# zs-pentagon-dip_0.net
KiCad netlist of a schematic drawn in Altium Designer
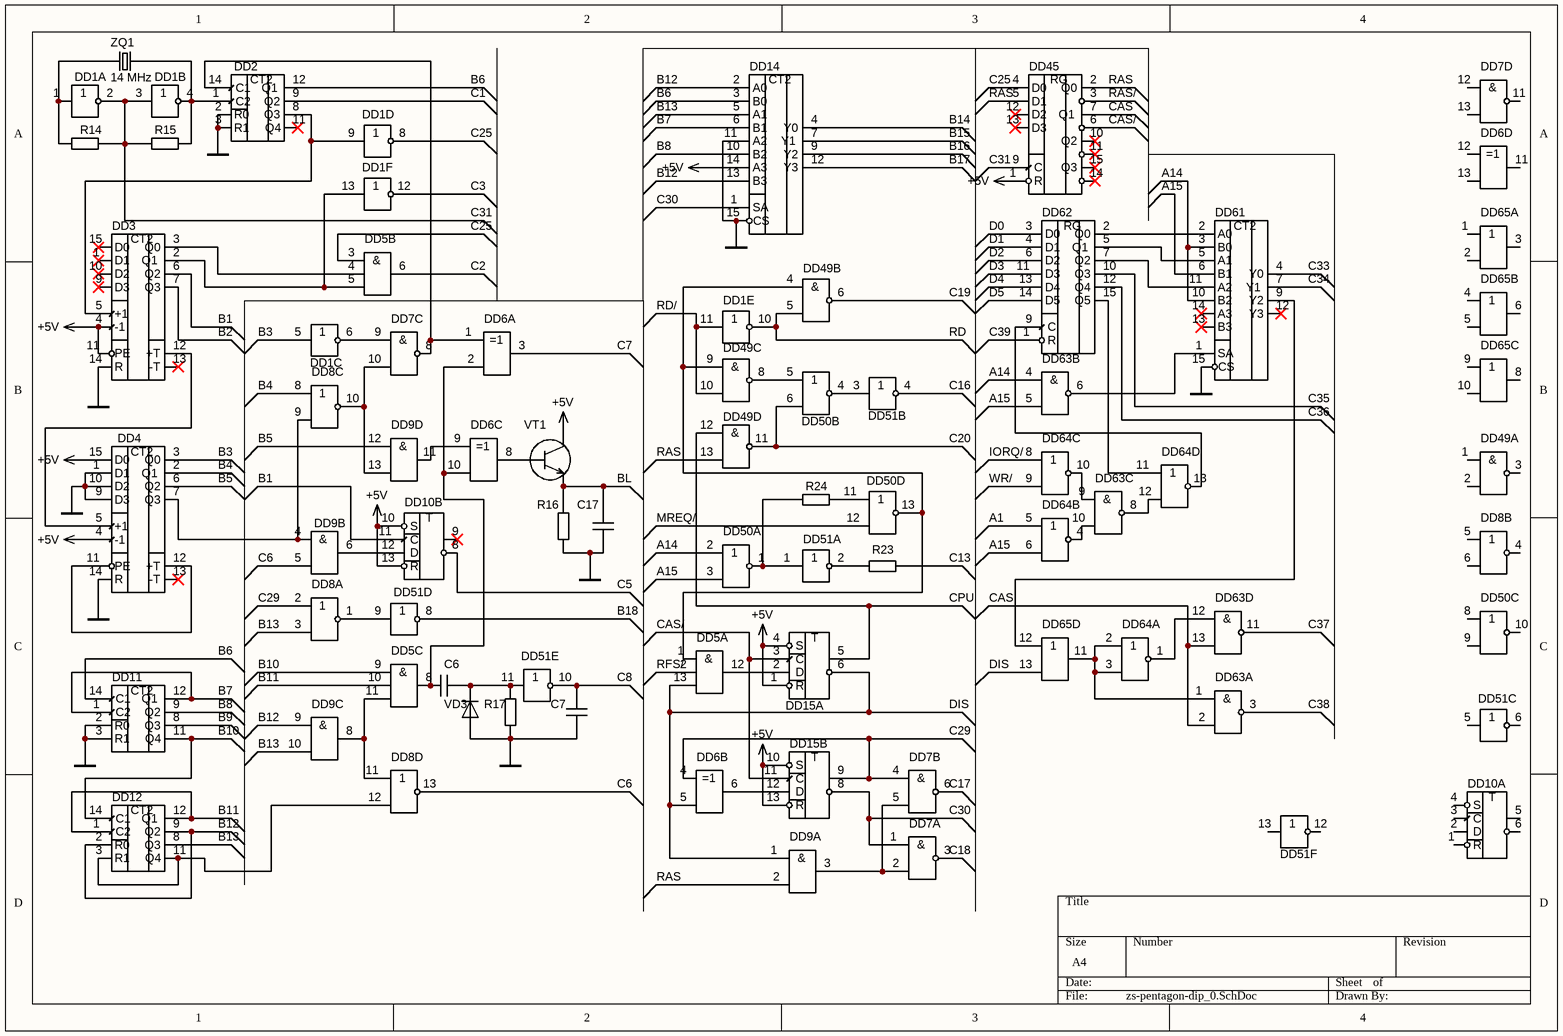
[diagram p0: zs-pentagon-dip_0.SchDoc]

(export (version "E")
  (design (tool "Eeschema 10.0.6"))
  (components
    (comp (ref "C6") (value "0.022 мкФ") (footprint "C0805") (libsource (lib "Capacitors") (part "CapCer")))
    (comp (ref "C7") (value "510 пФ") (footprint "C0805") (libsource (lib "Capacitors") (part "CapCer")))
    (comp (ref "C17") (value "1200 пФ") (footprint "C0805") (libsource (lib "Capacitors") (part "CapCer")))
    (comp (ref "DD1") (value "КР1533ЛН1") (footprint "DIP14") (libsource (lib "logic") (part "КР1533ЛН1")))
    (comp (ref "DD2") (value "КР1533ИЕ5") (footprint "DIP14") (libsource (lib "logic") (part "КР1533ИЕ5")))
    (comp (ref "DD3") (value "КР1533ИЕ7") (footprint "DIP16") (libsource (lib "logic") (part "КР1533ИЕ7")))
    (comp (ref "DD4") (value "КР1533ИЕ7") (footprint "DIP16") (libsource (lib "logic") (part "КР1533ИЕ7")))
    (comp (ref "DD5") (value "КР1533ЛИ3") (footprint "DIP14") (libsource (lib "logic") (part "КР1533ЛИ3")))
    (comp (ref "DD6") (value "КР1533ЛП5") (footprint "DIP14") (libsource (lib "logic") (part "КР1533ЛП5")))
    (comp (ref "DD7") (value "КР1533ЛA3") (footprint "DIP14") (libsource (lib "logic") (part "КР1533ЛA3")))
    (comp (ref "DD8") (value "КР1533ЛЕ1") (footprint "DIP14") (libsource (lib "logic") (part "КР1533ЛЕ1")))
    (comp (ref "DD9") (value "КР1533ЛИ1") (footprint "DIP14") (libsource (lib "logic") (part "КР1533ЛИ1")))
    (comp (ref "DD10") (value "КР1533ТМ2") (footprint "DIP14") (libsource (lib "logic") (part "КР1533ТМ2")))
    (comp (ref "DD11") (value "КР1533ИЕ5") (footprint "DIP14") (libsource (lib "logic") (part "КР1533ИЕ5")))
    (comp (ref "DD12") (value "КР1533ИЕ5") (footprint "DIP14") (libsource (lib "logic") (part "КР1533ИЕ5")))
    (comp (ref "DD14")
      (value "КР1533КП11А")
      (footprint "DIP16")
      (libsource (lib "logic") (part "КР1533КП11А"))
    )
    (comp (ref "DD15") (value "КР1533ТМ2") (footprint "DIP14") (libsource (lib "logic") (part "КР1533ТМ2")))
    (comp (ref "DD45") (value "КР1533ТМ8") (footprint "DIP16") (libsource (lib "logic") (part "КР1533ТМ8")))
    (comp (ref "DD49") (value "КР1533ЛA3") (footprint "DIP14") (libsource (lib "logic") (part "КР1533ЛA3")))
    (comp (ref "DD50") (value "КР1533ЛЕ1") (footprint "DIP14") (libsource (lib "logic") (part "КР1533ЛЕ1")))
    (comp (ref "DD51") (value "КР1533ЛН1") (footprint "DIP14") (libsource (lib "logic") (part "КР1533ЛН1")))
    (comp (ref "DD61")
      (value "КР1533КП11А")
      (footprint "DIP16")
      (libsource (lib "logic") (part "КР1533КП11А"))
    )
    (comp (ref "DD62") (value "КР1533ТМ9") (footprint "DIP16") (libsource (lib "logic") (part "КР1533ТМ9")))
    (comp (ref "DD63") (value "КР1533ЛA3") (footprint "DIP14") (libsource (lib "logic") (part "КР1533ЛA3")))
    (comp (ref "DD64") (value "КР1533ЛЕ1") (footprint "DIP14") (libsource (lib "logic") (part "КР1533ЛЕ1")))
    (comp (ref "DD65") (value "КР1533ЛЛ1") (footprint "DIP14") (libsource (lib "logic") (part "КР1533ЛЛ1")))
    (comp (ref "R14") (value "510 Ом") (footprint "R0603") (libsource (lib "Resistors") (part "Res")))
    (comp (ref "R15") (value "510 Ом") (footprint "R0603") (libsource (lib "Resistors") (part "Res")))
    (comp (ref "R16") (value "160 Ом") (footprint "R0603") (libsource (lib "Resistors") (part "Res")))
    (comp (ref "R17") (value "1 кОм") (footprint "R0603") (libsource (lib "Resistors") (part "Res")))
    (comp (ref "R23") (value "470 Ом") (footprint "R0603") (libsource (lib "Resistors") (part "Res")))
    (comp (ref "R24") (value "470 Ом") (footprint "R0603") (libsource (lib "Resistors") (part "Res")))
    (comp (ref "VD3")
      (value "1N4148W")
      (footprint "SODFL1608X70N")
      (libsource (lib "Diodes") (part "1N4148W"))
    )
    (comp (ref "VT1")
      (value "КТ315Б")
      (footprint "KT-13")
      (description "NPN Transistor")
      (libsource (lib "Transistors") (part "КТ315Б"))
    )
    (comp (ref "ZQ1")
      (value "14 MHz")
      (footprint "XTAL_HC-49U")
      (libsource (lib "Oscillators") (part "HC-49U_14M"))
    )
  )
  (nets
    (net (code "1") (name "+5V") (class "Default")
      (node (ref "DD10") (pin "10") (pinfunction "S_10") (pintype "passive"))
      (node (ref "DD10") (pin "13") (pinfunction "R_13") (pintype "passive"))
      (node (ref "DD14") (pin "14") (pinfunction "A3_14") (pintype "passive"))
      (node (ref "DD15") (pin "1") (pinfunction "R_1") (pintype "passive"))
      (node (ref "DD15") (pin "10") (pinfunction "S_10") (pintype "passive"))
      (node (ref "DD15") (pin "13") (pinfunction "R_13") (pintype "passive"))
      (node (ref "DD15") (pin "4") (pinfunction "S_4") (pintype "passive"))
      (node (ref "DD3") (pin "11") (pinfunction "PE_11") (pintype "passive"))
      (node (ref "DD3") (pin "4") (pinfunction "-1_4") (pintype "passive"))
      (node (ref "DD4") (pin "15") (pinfunction "D0_15") (pintype "passive"))
      (node (ref "DD4") (pin "4") (pinfunction "-1_4") (pintype "passive"))
      (node (ref "DD45") (pin "1") (pinfunction "R_1") (pintype "passive"))
      (node (ref "VT1") (pin "2") (pinfunction "C_2") (pintype "power_in"))
    )
    (net (code "2") (name "/A1") (class "Default") (node (ref "DD64") (pin "5") (pintype "passive")))
    (net (code "3") (name "/A14") (class "Default")
      (node (ref "DD50") (pin "2") (pintype "passive"))
      (node (ref "DD61") (pin "10") (pinfunction "B2_10") (pintype "passive"))
      (node (ref "DD61") (pin "3") (pinfunction "B0_3") (pintype "passive"))
      (node (ref "DD63") (pin "4") (pintype "passive"))
    )
    (net (code "4") (name "/A15") (class "Default")
      (node (ref "DD50") (pin "3") (pintype "passive"))
      (node (ref "DD61") (pin "6") (pinfunction "B1_6") (pintype "passive"))
      (node (ref "DD63") (pin "5") (pintype "passive"))
      (node (ref "DD64") (pin "6") (pintype "passive"))
    )
    (net (code "5") (name "/B1") (class "Default")
      (node (ref "DD10") (pin "11") (pinfunction "C_11") (pintype "passive"))
      (node (ref "DD3") (pin "6") (pinfunction "Q2_6") (pintype "passive"))
    )
    (net (code "6") (name "/B2") (class "Default")
      (node (ref "DD3") (pin "7") (pinfunction "Q3_7") (pintype "passive"))
    )
    (net (code "7") (name "/B3") (class "Default")
      (node (ref "DD1") (pin "5") (pintype "passive"))
      (node (ref "DD4") (pin "3") (pinfunction "Q0_3") (pintype "passive"))
    )
    (net (code "8") (name "/B4") (class "Default")
      (node (ref "DD4") (pin "2") (pinfunction "Q1_2") (pintype "passive"))
      (node (ref "DD8") (pin "8") (pintype "passive"))
    )
    (net (code "9") (name "/B5") (class "Default")
      (node (ref "DD4") (pin "6") (pinfunction "Q2_6") (pintype "passive"))
      (node (ref "DD9") (pin "12") (pintype "passive"))
    )
    (net (code "10") (name "/B6") (class "Default")
      (node (ref "DD11") (pin "14") (pinfunction "C1_14") (pintype "passive"))
      (node (ref "DD14") (pin "3") (pinfunction "B0_3") (pintype "passive"))
      (node (ref "DD2") (pin "12") (pinfunction "Q1_12") (pintype "passive"))
    )
    (net (code "11") (name "/B7") (class "Default")
      (node (ref "DD11") (pin "1") (pinfunction "C2_1") (pintype "passive"))
      (node (ref "DD11") (pin "12") (pinfunction "Q1_12") (pintype "passive"))
      (node (ref "DD14") (pin "6") (pinfunction "B1_6") (pintype "passive"))
    )
    (net (code "12") (name "/B8") (class "Default")
      (node (ref "DD11") (pin "9") (pinfunction "Q2_9") (pintype "passive"))
      (node (ref "DD14") (pin "10") (pinfunction "B2_10") (pintype "passive"))
    )
    (net (code "13") (name "/B9") (class "Default")
      (node (ref "DD11") (pin "8") (pinfunction "Q3_8") (pintype "passive"))
    )
    (net (code "14") (name "/B10") (class "Default")
      (node (ref "DD11") (pin "11") (pinfunction "Q4_11") (pintype "passive"))
      (node (ref "DD12") (pin "14") (pinfunction "C1_14") (pintype "passive"))
      (node (ref "DD5") (pin "9") (pintype "passive"))
    )
    (net (code "15") (name "/B11") (class "Default")
      (node (ref "DD12") (pin "1") (pinfunction "C2_1") (pintype "passive"))
      (node (ref "DD12") (pin "12") (pinfunction "Q1_12") (pintype "passive"))
      (node (ref "DD5") (pin "10") (pintype "passive"))
    )
    (net (code "16") (name "/B12") (class "Default")
      (node (ref "DD12") (pin "2") (pinfunction "R0_2") (pintype "passive"))
      (node (ref "DD12") (pin "9") (pinfunction "Q2_9") (pintype "passive"))
      (node (ref "DD14") (pin "13") (pinfunction "B3_13") (pintype "passive"))
      (node (ref "DD14") (pin "2") (pinfunction "A0_2") (pintype "passive"))
      (node (ref "DD9") (pin "9") (pintype "passive"))
    )
    (net (code "17") (name "/B13") (class "Default")
      (node (ref "DD12") (pin "8") (pinfunction "Q3_8") (pintype "passive"))
      (node (ref "DD14") (pin "5") (pinfunction "A1_5") (pintype "passive"))
      (node (ref "DD8") (pin "3") (pintype "passive"))
      (node (ref "DD9") (pin "10") (pintype "passive"))
    )
    (net (code "18") (name "/B14") (class "Default")
      (node (ref "DD14") (pin "4") (pinfunction "Y0_4") (pintype "passive"))
    )
    (net (code "19") (name "/B15") (class "Default")
      (node (ref "DD14") (pin "7") (pinfunction "Y1_7") (pintype "passive"))
    )
    (net (code "20") (name "/B16") (class "Default")
      (node (ref "DD14") (pin "9") (pinfunction "Y2_9") (pintype "passive"))
    )
    (net (code "21") (name "/B17") (class "Default")
      (node (ref "DD14") (pin "12") (pinfunction "Y3_12") (pintype "passive"))
    )
    (net (code "22") (name "/B18") (class "Default") (node (ref "DD51") (pin "8") (pintype "passive")))
    (net (code "23") (name "/BL") (class "Default")
      (node (ref "C17") (pin "2") (pinfunction "2_2") (pintype "passive"))
      (node (ref "R16") (pin "2") (pinfunction "2_2") (pintype "passive"))
      (node (ref "VT1") (pin "1") (pinfunction "E_1") (pintype "power_in"))
    )
    (net (code "24") (name "/C1") (class "Default")
      (node (ref "DD2") (pin "9") (pinfunction "Q2_9") (pintype "passive"))
    )
    (net (code "25") (name "/C2") (class "Default") (node (ref "DD5") (pin "6") (pintype "passive")))
    (net (code "26") (name "/C3") (class "Default") (node (ref "DD1") (pin "12") (pintype "passive")))
    (net (code "27") (name "/C5") (class "Default") (node (ref "DD10") (pin "8") (pintype "passive")))
    (net (code "28") (name "/C6") (class "Default")
      (node (ref "DD8") (pin "13") (pintype "passive"))
      (node (ref "DD9") (pin "5") (pintype "passive"))
    )
    (net (code "29") (name "/C7") (class "Default") (node (ref "DD6") (pin "3") (pintype "passive")))
    (net (code "30") (name "/C8") (class "Default")
      (node (ref "C7") (pin "1") (pinfunction "1_1") (pintype "passive"))
      (node (ref "DD51") (pin "10") (pintype "passive"))
    )
    (net (code "31") (name "/C13") (class "Default")
      (node (ref "R23") (pin "1") (pinfunction "1_1") (pintype "passive"))
    )
    (net (code "32") (name "/C16") (class "Default") (node (ref "DD51") (pin "4") (pintype "passive")))
    (net (code "33") (name "/C17") (class "Default") (node (ref "DD7") (pin "6") (pintype "passive")))
    (net (code "34") (name "/C18") (class "Default") (node (ref "DD7") (pin "3") (pintype "passive")))
    (net (code "35") (name "/C19") (class "Default") (node (ref "DD49") (pin "6") (pintype "passive")))
    (net (code "36") (name "/C20") (class "Default")
      (node (ref "DD49") (pin "11") (pintype "passive"))
      (node (ref "DD50") (pin "6") (pintype "passive"))
    )
    (net (code "37") (name "/C25") (class "Default")
      (node (ref "DD1") (pin "8") (pintype "passive"))
      (node (ref "DD45") (pin "4") (pinfunction "D0_4") (pintype "passive"))
      (node (ref "DD5") (pin "3") (pintype "passive"))
    )
    (net (code "38") (name "/C29") (class "Default")
      (node (ref "DD15") (pin "9") (pintype "passive"))
      (node (ref "DD6") (pin "4") (pintype "passive"))
      (node (ref "DD7") (pin "4") (pintype "passive"))
      (node (ref "DD8") (pin "2") (pintype "passive"))
    )
    (net (code "39") (name "/C30") (class "Default")
      (node (ref "DD14") (pin "1") (pinfunction "SA_1") (pintype "passive"))
      (node (ref "DD15") (pin "8") (pintype "passive"))
      (node (ref "DD7") (pin "1") (pintype "passive"))
    )
    (net (code "40") (name "/C31") (class "Default")
      (node (ref "DD1") (pin "2") (pintype "passive"))
      (node (ref "DD1") (pin "3") (pintype "passive"))
      (node (ref "DD45") (pin "9") (pinfunction "C_9") (pintype "passive"))
      (node (ref "R14") (pin "2") (pinfunction "2_2") (pintype "passive"))
      (node (ref "R15") (pin "1") (pinfunction "1_1") (pintype "passive"))
    )
    (net (code "41") (name "/C33") (class "Default")
      (node (ref "DD61") (pin "4") (pinfunction "Y0_4") (pintype "passive"))
    )
    (net (code "42") (name "/C34") (class "Default")
      (node (ref "DD61") (pin "7") (pinfunction "Y1_7") (pintype "passive"))
    )
    (net (code "43") (name "/C35") (class "Default")
      (node (ref "DD62") (pin "10") (pinfunction "Q3_10") (pintype "passive"))
    )
    (net (code "44") (name "/C36") (class "Default")
      (node (ref "DD62") (pin "12") (pinfunction "Q4_12") (pintype "passive"))
    )
    (net (code "45") (name "/C37") (class "Default") (node (ref "DD63") (pin "11") (pintype "passive")))
    (net (code "46") (name "/C38") (class "Default") (node (ref "DD63") (pin "3") (pintype "passive")))
    (net (code "47") (name "/C39") (class "Default")
      (node (ref "DD62") (pin "1") (pinfunction "R_1") (pintype "passive"))
    )
    (net (code "48") (name "/CAS") (class "Default")
      (node (ref "DD45") (pin "7") (pinfunction "Q1_7") (pintype "passive"))
      (node (ref "DD63") (pin "13") (pintype "passive"))
      (node (ref "DD63") (pin "2") (pintype "passive"))
    )
    (net (code "49") (name "/CAS{slash}") (class "Default")
      (node (ref "DD15") (pin "11") (pinfunction "C_11") (pintype "passive"))
      (node (ref "DD15") (pin "3") (pinfunction "C_3") (pintype "passive"))
      (node (ref "DD45") (pin "6") (pintype "passive"))
    )
    (net (code "50") (name "/CPU") (class "Default")
      (node (ref "DD15") (pin "5") (pintype "passive"))
      (node (ref "DD49") (pin "12") (pintype "passive"))
    )
    (net (code "51") (name "/D0") (class "Default")
      (node (ref "DD62") (pin "3") (pinfunction "D0_3") (pintype "passive"))
    )
    (net (code "52") (name "/D1") (class "Default")
      (node (ref "DD62") (pin "4") (pinfunction "D1_4") (pintype "passive"))
    )
    (net (code "53") (name "/D2") (class "Default")
      (node (ref "DD62") (pin "6") (pinfunction "D2_6") (pintype "passive"))
    )
    (net (code "54") (name "/D3") (class "Default")
      (node (ref "DD62") (pin "11") (pinfunction "D3_11") (pintype "passive"))
    )
    (net (code "55") (name "/D4") (class "Default")
      (node (ref "DD62") (pin "13") (pinfunction "D4_13") (pintype "passive"))
    )
    (net (code "56") (name "/D5") (class "Default")
      (node (ref "DD62") (pin "14") (pinfunction "D5_14") (pintype "passive"))
    )
    (net (code "57") (name "/DIS") (class "Default")
      (node (ref "DD15") (pin "6") (pintype "passive"))
      (node (ref "DD5") (pin "13") (pintype "passive"))
      (node (ref "DD6") (pin "5") (pintype "passive"))
      (node (ref "DD65") (pin "13") (pintype "passive"))
      (node (ref "DD9") (pin "1") (pintype "passive"))
    )
    (net (code "58") (name "/IORQ{slash}") (class "Default")
      (node (ref "DD64") (pin "8") (pintype "passive"))
    )
    (net (code "59") (name "/MREQ{slash}") (class "Default")
      (node (ref "DD50") (pin "12") (pintype "passive"))
    )
    (net (code "60") (name "/RAS") (class "Default")
      (node (ref "DD45") (pin "2") (pinfunction "Q0_2") (pintype "passive"))
      (node (ref "DD45") (pin "5") (pinfunction "D1_5") (pintype "passive"))
      (node (ref "DD49") (pin "13") (pintype "passive"))
      (node (ref "DD9") (pin "2") (pintype "passive"))
    )
    (net (code "61") (name "/RAS{slash}") (class "Default") (node (ref "DD45") (pin "3") (pintype "passive")))
    (net (code "62") (name "/RD") (class "Default")
      (node (ref "DD1") (pin "10") (pintype "passive"))
      (node (ref "DD49") (pin "5") (pintype "passive"))
    )
    (net (code "63") (name "/RD{slash}") (class "Default")
      (node (ref "DD1") (pin "11") (pintype "passive"))
      (node (ref "DD49") (pin "10") (pintype "passive"))
    )
    (net (code "64") (name "/RFS{slash}") (class "Default") (node (ref "DD5") (pin "2") (pintype "passive")))
    (net (code "65") (name "/WR{slash}") (class "Default") (node (ref "DD64") (pin "9") (pintype "passive")))
    (net (code "66") (name "GND") (class "Default")
      (node (ref "C17") (pin "1") (pinfunction "1_1") (pintype "passive"))
      (node (ref "C7") (pin "2") (pinfunction "2_2") (pintype "passive"))
      (node (ref "DD1") (pin "7") (pinfunction "GND_7") (pintype "power_in"))
      (node (ref "DD10") (pin "7") (pinfunction "GND_7") (pintype "power_in"))
      (node (ref "DD11") (pin "10") (pinfunction "GND_10") (pintype "power_in"))
      (node (ref "DD11") (pin "2") (pinfunction "R0_2") (pintype "passive"))
      (node (ref "DD11") (pin "3") (pinfunction "R1_3") (pintype "passive"))
      (node (ref "DD12") (pin "10") (pinfunction "GND_10") (pintype "power_in"))
      (node (ref "DD14") (pin "11") (pinfunction "A2_11") (pintype "passive"))
      (node (ref "DD14") (pin "15") (pinfunction "CS_15") (pintype "passive"))
      (node (ref "DD14") (pin "8") (pinfunction "GND_8") (pintype "power_in"))
      (node (ref "DD15") (pin "7") (pinfunction "GND_7") (pintype "power_in"))
      (node (ref "DD2") (pin "10") (pinfunction "GND_10") (pintype "power_in"))
      (node (ref "DD2") (pin "2") (pinfunction "R0_2") (pintype "passive"))
      (node (ref "DD2") (pin "3") (pinfunction "R1_3") (pintype "passive"))
      (node (ref "DD3") (pin "14") (pinfunction "R_14") (pintype "passive"))
      (node (ref "DD3") (pin "8") (pinfunction "GND_8") (pintype "power_in"))
      (node (ref "DD4") (pin "1") (pinfunction "D1_1") (pintype "passive"))
      (node (ref "DD4") (pin "10") (pinfunction "D2_10") (pintype "passive"))
      (node (ref "DD4") (pin "14") (pinfunction "R_14") (pintype "passive"))
      (node (ref "DD4") (pin "8") (pinfunction "GND_8") (pintype "power_in"))
      (node (ref "DD4") (pin "9") (pinfunction "D3_9") (pintype "passive"))
      (node (ref "DD45") (pin "8") (pinfunction "GND_8") (pintype "power_in"))
      (node (ref "DD49") (pin "7") (pinfunction "GND_7") (pintype "power_in"))
      (node (ref "DD5") (pin "7") (pinfunction "GND_7") (pintype "power_in"))
      (node (ref "DD50") (pin "7") (pinfunction "GND_7") (pintype "power_in"))
      (node (ref "DD51") (pin "7") (pinfunction "GND_7") (pintype "power_in"))
      (node (ref "DD6") (pin "7") (pinfunction "GND_7") (pintype "power_in"))
      (node (ref "DD61") (pin "15") (pinfunction "CS_15") (pintype "passive"))
      (node (ref "DD61") (pin "8") (pinfunction "GND_8") (pintype "power_in"))
      (node (ref "DD62") (pin "8") (pinfunction "GND_8") (pintype "power_in"))
      (node (ref "DD63") (pin "7") (pinfunction "GND_7") (pintype "power_in"))
      (node (ref "DD64") (pin "7") (pinfunction "GND_7") (pintype "power_in"))
      (node (ref "DD65") (pin "7") (pinfunction "GND_7") (pintype "power_in"))
      (node (ref "DD7") (pin "7") (pinfunction "GND_7") (pintype "power_in"))
      (node (ref "DD8") (pin "7") (pinfunction "GND_7") (pintype "power_in"))
      (node (ref "DD9") (pin "7") (pinfunction "GND_7") (pintype "power_in"))
      (node (ref "R16") (pin "1") (pinfunction "1_1") (pintype "passive"))
      (node (ref "R17") (pin "1") (pinfunction "1_1") (pintype "passive"))
      (node (ref "VD3") (pin "A") (pinfunction "A_A") (pintype "passive"))
    )
    (net (code "67") (name "Net-(C6-Pad1)") (class "Default")
      (node (ref "C6") (pin "1") (pinfunction "1_1") (pintype "passive"))
      (node (ref "DD51") (pin "11") (pintype "passive"))
      (node (ref "R17") (pin "2") (pinfunction "2_2") (pintype "passive"))
      (node (ref "VD3") (pin "C") (pinfunction "C_C") (pintype "passive"))
    )
    (net (code "68") (name "Net-(C6-Pad2)") (class "Default")
      (node (ref "C6") (pin "2") (pinfunction "2_2") (pintype "passive"))
      (node (ref "DD5") (pin "8") (pintype "passive"))
      (node (ref "DD6") (pin "10") (pintype "passive"))
      (node (ref "DD6") (pin "2") (pintype "passive"))
    )
    (net (code "69") (name "Net-(DD1-Pad1)") (class "Default")
      (node (ref "DD1") (pin "1") (pintype "passive"))
      (node (ref "R14") (pin "1") (pinfunction "1_1") (pintype "passive"))
      (node (ref "ZQ1") (pin "2") (pinfunction "2_2") (pintype "passive"))
    )
    (net (code "70") (name "Net-(DD1-Pad6)") (class "Default")
      (node (ref "DD1") (pin "6") (pintype "passive"))
      (node (ref "DD7") (pin "9") (pintype "passive"))
    )
    (net (code "71") (name "Net-(DD2-C1)") (class "Default")
      (node (ref "DD2") (pin "14") (pinfunction "C1_14") (pintype "passive"))
      (node (ref "DD6") (pin "1") (pintype "passive"))
      (node (ref "DD7") (pin "8") (pintype "passive"))
    )
    (net (code "72") (name "Net-(DD2-C2)") (class "Default")
      (node (ref "DD1") (pin "4") (pintype "passive"))
      (node (ref "DD2") (pin "1") (pinfunction "C2_1") (pintype "passive"))
      (node (ref "R15") (pin "2") (pinfunction "2_2") (pintype "passive"))
      (node (ref "ZQ1") (pin "1") (pinfunction "1_1") (pintype "passive"))
    )
    (net (code "73") (name "Net-(DD2-Q3)") (class "Default")
      (node (ref "DD1") (pin "9") (pintype "passive"))
      (node (ref "DD2") (pin "8") (pinfunction "Q3_8") (pintype "passive"))
      (node (ref "DD3") (pin "5") (pinfunction "+1_5") (pintype "passive"))
    )
    (net (code "74") (name "Net-(DD3-+T)") (class "Default")
      (node (ref "DD3") (pin "12") (pinfunction "+T_12") (pintype "passive"))
      (node (ref "DD4") (pin "5") (pinfunction "+1_5") (pintype "passive"))
    )
    (net (code "75") (name "Net-(DD3-Q0)") (class "Default")
      (node (ref "DD3") (pin "3") (pinfunction "Q0_3") (pintype "passive"))
      (node (ref "DD5") (pin "4") (pintype "passive"))
    )
    (net (code "76") (name "Net-(DD3-Q1)") (class "Default")
      (node (ref "DD1") (pin "13") (pintype "passive"))
      (node (ref "DD3") (pin "2") (pinfunction "Q1_2") (pintype "passive"))
      (node (ref "DD5") (pin "5") (pintype "passive"))
    )
    (net (code "77") (name "Net-(DD4-+T)") (class "Default")
      (node (ref "DD4") (pin "11") (pinfunction "PE_11") (pintype "passive"))
      (node (ref "DD4") (pin "12") (pinfunction "+T_12") (pintype "passive"))
    )
    (net (code "78") (name "Net-(DD4-Q3)") (class "Default")
      (node (ref "DD4") (pin "7") (pinfunction "Q3_7") (pintype "passive"))
      (node (ref "DD8") (pin "9") (pintype "passive"))
      (node (ref "DD9") (pin "4") (pintype "passive"))
    )
    (net (code "79") (name "Net-(DD5-Pad11)") (class "Default")
      (node (ref "DD5") (pin "11") (pintype "passive"))
      (node (ref "DD8") (pin "11") (pintype "passive"))
      (node (ref "DD9") (pin "8") (pintype "passive"))
    )
    (net (code "80") (name "Net-(DD6-Pad9)") (class "Default")
      (node (ref "DD6") (pin "9") (pintype "passive"))
      (node (ref "DD9") (pin "11") (pintype "passive"))
    )
    (net (code "81") (name "Net-(DD7-Pad2)") (class "Default")
      (node (ref "DD7") (pin "2") (pintype "passive"))
      (node (ref "DD7") (pin "5") (pintype "passive"))
      (node (ref "DD9") (pin "3") (pintype "passive"))
    )
    (net (code "82") (name "Net-(DD7-Pad10)") (class "Default")
      (node (ref "DD7") (pin "10") (pintype "passive"))
      (node (ref "DD8") (pin "10") (pintype "passive"))
      (node (ref "DD9") (pin "13") (pintype "passive"))
    )
    (net (code "83") (name "Net-(DD10B-D)") (class "Default")
      (node (ref "DD10") (pin "12") (pinfunction "D_12") (pintype "passive"))
      (node (ref "DD9") (pin "6") (pintype "passive"))
    )
    (net (code "84") (name "Net-(DD12-Q4)") (class "Default")
      (node (ref "DD12") (pin "11") (pinfunction "Q4_11") (pintype "passive"))
      (node (ref "DD12") (pin "3") (pinfunction "R1_3") (pintype "passive"))
      (node (ref "DD8") (pin "12") (pintype "passive"))
    )
    (net (code "85") (name "Net-(DD15A-D)") (class "Default")
      (node (ref "DD15") (pin "2") (pinfunction "D_2") (pintype "passive"))
      (node (ref "DD5") (pin "12") (pintype "passive"))
    )
    (net (code "86") (name "Net-(DD15B-D)") (class "Default")
      (node (ref "DD15") (pin "12") (pinfunction "D_12") (pintype "passive"))
      (node (ref "DD6") (pin "6") (pintype "passive"))
    )
    (net (code "87") (name "Net-(DD49-Pad4)") (class "Default")
      (node (ref "DD49") (pin "4") (pintype "passive"))
      (node (ref "DD49") (pin "9") (pintype "passive"))
      (node (ref "DD5") (pin "1") (pintype "passive"))
      (node (ref "DD50") (pin "13") (pintype "passive"))
    )
    (net (code "88") (name "Net-(DD49-Pad8)") (class "Default")
      (node (ref "DD49") (pin "8") (pintype "passive"))
      (node (ref "DD50") (pin "5") (pintype "passive"))
    )
    (net (code "89") (name "Net-(DD50-Pad1)") (class "Default")
      (node (ref "DD50") (pin "1") (pintype "passive"))
      (node (ref "DD51") (pin "1") (pintype "passive"))
      (node (ref "R24") (pin "2") (pinfunction "2_2") (pintype "passive"))
    )
    (net (code "90") (name "Net-(DD50-Pad4)") (class "Default")
      (node (ref "DD50") (pin "4") (pintype "passive"))
      (node (ref "DD51") (pin "3") (pintype "passive"))
    )
    (net (code "91") (name "Net-(DD50-Pad11)") (class "Default")
      (node (ref "DD50") (pin "11") (pintype "passive"))
      (node (ref "R24") (pin "1") (pinfunction "1_1") (pintype "passive"))
    )
    (net (code "92") (name "Net-(DD51-Pad2)") (class "Default")
      (node (ref "DD51") (pin "2") (pintype "passive"))
      (node (ref "R23") (pin "2") (pinfunction "2_2") (pintype "passive"))
    )
    (net (code "93") (name "Net-(DD51-Pad9)") (class "Default")
      (node (ref "DD51") (pin "9") (pintype "passive"))
      (node (ref "DD8") (pin "1") (pintype "passive"))
    )
    (net (code "94") (name "Net-(DD61-A0)") (class "Default")
      (node (ref "DD61") (pin "2") (pinfunction "A0_2") (pintype "passive"))
      (node (ref "DD62") (pin "2") (pinfunction "Q0_2") (pintype "passive"))
    )
    (net (code "95") (name "Net-(DD61-A1)") (class "Default")
      (node (ref "DD61") (pin "5") (pinfunction "A1_5") (pintype "passive"))
      (node (ref "DD62") (pin "5") (pinfunction "Q1_5") (pintype "passive"))
    )
    (net (code "96") (name "Net-(DD61-A2)") (class "Default")
      (node (ref "DD61") (pin "11") (pinfunction "A2_11") (pintype "passive"))
      (node (ref "DD62") (pin "7") (pinfunction "Q2_7") (pintype "passive"))
    )
    (net (code "97") (name "Net-(DD61-SA)") (class "Default")
      (node (ref "DD61") (pin "1") (pinfunction "SA_1") (pintype "passive"))
      (node (ref "DD63") (pin "6") (pintype "passive"))
    )
    (net (code "98") (name "Net-(DD61-Y2)") (class "Default")
      (node (ref "DD61") (pin "9") (pinfunction "Y2_9") (pintype "passive"))
      (node (ref "DD65") (pin "12") (pintype "passive"))
    )
    (net (code "99") (name "Net-(DD62-C)") (class "Default")
      (node (ref "DD62") (pin "9") (pinfunction "C_9") (pintype "passive"))
      (node (ref "DD64") (pin "13") (pintype "passive"))
    )
    (net (code "100") (name "Net-(DD62-Q5)") (class "Default")
      (node (ref "DD62") (pin "15") (pinfunction "Q5_15") (pintype "passive"))
      (node (ref "DD64") (pin "11") (pintype "passive"))
    )
    (net (code "101") (name "Net-(DD63-Pad1)") (class "Default")
      (node (ref "DD63") (pin "1") (pintype "passive"))
      (node (ref "DD64") (pin "2") (pintype "passive"))
      (node (ref "DD64") (pin "3") (pintype "passive"))
      (node (ref "DD65") (pin "11") (pintype "passive"))
    )
    (net (code "102") (name "Net-(DD63-Pad8)") (class "Default")
      (node (ref "DD63") (pin "8") (pintype "passive"))
      (node (ref "DD64") (pin "12") (pintype "passive"))
    )
    (net (code "103") (name "Net-(DD63-Pad9)") (class "Default")
      (node (ref "DD63") (pin "9") (pintype "passive"))
      (node (ref "DD64") (pin "10") (pintype "passive"))
    )
    (net (code "104") (name "Net-(DD63-Pad10)") (class "Default")
      (node (ref "DD63") (pin "10") (pintype "passive"))
      (node (ref "DD64") (pin "4") (pintype "passive"))
    )
    (net (code "105") (name "Net-(DD63-Pad12)") (class "Default")
      (node (ref "DD63") (pin "12") (pintype "passive"))
      (node (ref "DD64") (pin "1") (pintype "passive"))
    )
    (net (code "106") (name "Net-(VT1-B)") (class "Default")
      (node (ref "DD6") (pin "8") (pintype "passive"))
      (node (ref "VT1") (pin "3") (pinfunction "B_3") (pintype "power_in"))
    )
    (net (code "107") (name "VCC") (class "Default")
      (node (ref "DD1") (pin "14") (pinfunction "VCC_14") (pintype "power_in"))
      (node (ref "DD10") (pin "14") (pinfunction "VCC_14") (pintype "power_in"))
      (node (ref "DD11") (pin "5") (pinfunction "VCC_5") (pintype "power_in"))
      (node (ref "DD12") (pin "5") (pinfunction "VCC_5") (pintype "power_in"))
      (node (ref "DD14") (pin "16") (pinfunction "VCC_16") (pintype "power_in"))
      (node (ref "DD15") (pin "14") (pinfunction "VCC_14") (pintype "power_in"))
      (node (ref "DD2") (pin "5") (pinfunction "VCC_5") (pintype "power_in"))
      (node (ref "DD3") (pin "16") (pinfunction "VCC_16") (pintype "power_in"))
      (node (ref "DD4") (pin "16") (pinfunction "VCC_16") (pintype "power_in"))
      (node (ref "DD45") (pin "16") (pinfunction "VCC_16") (pintype "power_in"))
      (node (ref "DD49") (pin "14") (pinfunction "VCC_14") (pintype "power_in"))
      (node (ref "DD5") (pin "14") (pinfunction "VCC_14") (pintype "power_in"))
      (node (ref "DD50") (pin "14") (pinfunction "VCC_14") (pintype "power_in"))
      (node (ref "DD51") (pin "14") (pinfunction "VCC_14") (pintype "power_in"))
      (node (ref "DD6") (pin "14") (pinfunction "VCC_14") (pintype "power_in"))
      (node (ref "DD61") (pin "16") (pinfunction "VCC_16") (pintype "power_in"))
      (node (ref "DD62") (pin "16") (pinfunction "VCC_16") (pintype "power_in"))
      (node (ref "DD63") (pin "14") (pinfunction "VCC_14") (pintype "power_in"))
      (node (ref "DD64") (pin "14") (pinfunction "VCC_14") (pintype "power_in"))
      (node (ref "DD65") (pin "14") (pinfunction "VCC_14") (pintype "power_in"))
      (node (ref "DD7") (pin "14") (pinfunction "VCC_14") (pintype "power_in"))
      (node (ref "DD8") (pin "14") (pinfunction "VCC_14") (pintype "power_in"))
      (node (ref "DD9") (pin "14") (pinfunction "VCC_14") (pintype "power_in"))
    )
    (net (code "108") (name "unconnected-(DD2-Q4-Pad11)") (class "Default")
      (node (ref "DD2") (pin "11") (pinfunction "Q4_11") (pintype "passive+no_connect"))
    )
    (net (code "109") (name "unconnected-(DD3--T-Pad13)") (class "Default")
      (node (ref "DD3") (pin "13") (pinfunction "-T_13") (pintype "passive+no_connect"))
    )
    (net (code "110") (name "unconnected-(DD3-D0-Pad15)") (class "Default")
      (node (ref "DD3") (pin "15") (pinfunction "D0_15") (pintype "passive+no_connect"))
    )
    (net (code "111") (name "unconnected-(DD3-D1-Pad1)") (class "Default")
      (node (ref "DD3") (pin "1") (pinfunction "D1_1") (pintype "passive+no_connect"))
    )
    (net (code "112") (name "unconnected-(DD3-D2-Pad10)") (class "Default")
      (node (ref "DD3") (pin "10") (pinfunction "D2_10") (pintype "passive+no_connect"))
    )
    (net (code "113") (name "unconnected-(DD3-D3-Pad9)") (class "Default")
      (node (ref "DD3") (pin "9") (pinfunction "D3_9") (pintype "passive+no_connect"))
    )
    (net (code "114") (name "unconnected-(DD4--T-Pad13)") (class "Default")
      (node (ref "DD4") (pin "13") (pinfunction "-T_13") (pintype "passive+no_connect"))
    )
    (net (code "115") (name "unconnected-(DD6-Pad11)") (class "Default")
      (node (ref "DD6") (pin "11") (pintype "passive"))
    )
    (net (code "116") (name "unconnected-(DD6-Pad12)") (class "Default")
      (node (ref "DD6") (pin "12") (pintype "passive"))
    )
    (net (code "117") (name "unconnected-(DD6-Pad13)") (class "Default")
      (node (ref "DD6") (pin "13") (pintype "passive"))
    )
    (net (code "118") (name "unconnected-(DD7-Pad11)") (class "Default")
      (node (ref "DD7") (pin "11") (pintype "passive"))
    )
    (net (code "119") (name "unconnected-(DD7-Pad12)") (class "Default")
      (node (ref "DD7") (pin "12") (pintype "passive"))
    )
    (net (code "120") (name "unconnected-(DD7-Pad13)") (class "Default")
      (node (ref "DD7") (pin "13") (pintype "passive"))
    )
    (net (code "121") (name "unconnected-(DD8-Pad4)") (class "Default")
      (node (ref "DD8") (pin "4") (pintype "passive"))
    )
    (net (code "122") (name "unconnected-(DD8-Pad5)") (class "Default")
      (node (ref "DD8") (pin "5") (pintype "passive"))
    )
    (net (code "123") (name "unconnected-(DD8-Pad6)") (class "Default")
      (node (ref "DD8") (pin "6") (pintype "passive"))
    )
    (net (code "124") (name "unconnected-(DD10-Pad5)") (class "Default")
      (node (ref "DD10") (pin "5") (pintype "passive"))
    )
    (net (code "125") (name "unconnected-(DD10-Pad6)") (class "Default")
      (node (ref "DD10") (pin "6") (pintype "passive"))
    )
    (net (code "126") (name "unconnected-(DD10-Pad9)") (class "Default")
      (node (ref "DD10") (pin "9") (pintype "passive+no_connect"))
    )
    (net (code "127") (name "unconnected-(DD10A-C-Pad3)") (class "Default")
      (node (ref "DD10") (pin "3") (pinfunction "C_3") (pintype "passive"))
    )
    (net (code "128") (name "unconnected-(DD10A-D-Pad2)") (class "Default")
      (node (ref "DD10") (pin "2") (pinfunction "D_2") (pintype "passive"))
    )
    (net (code "129") (name "unconnected-(DD10A-R-Pad1)") (class "Default")
      (node (ref "DD10") (pin "1") (pinfunction "R_1") (pintype "passive"))
    )
    (net (code "130") (name "unconnected-(DD10A-S-Pad4)") (class "Default")
      (node (ref "DD10") (pin "4") (pinfunction "S_4") (pintype "passive"))
    )
    (net (code "131") (name "unconnected-(DD45-D2-Pad12)") (class "Default")
      (node (ref "DD45") (pin "12") (pinfunction "D2_12") (pintype "passive+no_connect"))
    )
    (net (code "132") (name "unconnected-(DD45-D3-Pad13)") (class "Default")
      (node (ref "DD45") (pin "13") (pinfunction "D3_13") (pintype "passive+no_connect"))
    )
    (net (code "133") (name "unconnected-(DD45-Pad11)") (class "Default")
      (node (ref "DD45") (pin "11") (pintype "passive+no_connect"))
    )
    (net (code "134") (name "unconnected-(DD45-Pad14)") (class "Default")
      (node (ref "DD45") (pin "14") (pintype "passive+no_connect"))
    )
    (net (code "135") (name "unconnected-(DD45-Q2-Pad10)") (class "Default")
      (node (ref "DD45") (pin "10") (pinfunction "Q2_10") (pintype "passive+no_connect"))
    )
    (net (code "136") (name "unconnected-(DD45-Q3-Pad15)") (class "Default")
      (node (ref "DD45") (pin "15") (pinfunction "Q3_15") (pintype "passive+no_connect"))
    )
    (net (code "137") (name "unconnected-(DD49-Pad1)") (class "Default")
      (node (ref "DD49") (pin "1") (pintype "passive"))
    )
    (net (code "138") (name "unconnected-(DD49-Pad2)") (class "Default")
      (node (ref "DD49") (pin "2") (pintype "passive"))
    )
    (net (code "139") (name "unconnected-(DD49-Pad3)") (class "Default")
      (node (ref "DD49") (pin "3") (pintype "passive"))
    )
    (net (code "140") (name "unconnected-(DD50-Pad8)") (class "Default")
      (node (ref "DD50") (pin "8") (pintype "passive"))
    )
    (net (code "141") (name "unconnected-(DD50-Pad9)") (class "Default")
      (node (ref "DD50") (pin "9") (pintype "passive"))
    )
    (net (code "142") (name "unconnected-(DD50-Pad10)") (class "Default")
      (node (ref "DD50") (pin "10") (pintype "passive"))
    )
    (net (code "143") (name "unconnected-(DD51-Pad5)") (class "Default")
      (node (ref "DD51") (pin "5") (pintype "passive"))
    )
    (net (code "144") (name "unconnected-(DD51-Pad6)") (class "Default")
      (node (ref "DD51") (pin "6") (pintype "passive"))
    )
    (net (code "145") (name "unconnected-(DD51-Pad12)") (class "Default")
      (node (ref "DD51") (pin "12") (pintype "passive"))
    )
    (net (code "146") (name "unconnected-(DD51-Pad13)") (class "Default")
      (node (ref "DD51") (pin "13") (pintype "passive"))
    )
    (net (code "147") (name "unconnected-(DD61-A3-Pad14)") (class "Default")
      (node (ref "DD61") (pin "14") (pinfunction "A3_14") (pintype "passive+no_connect"))
    )
    (net (code "148") (name "unconnected-(DD61-B3-Pad13)") (class "Default")
      (node (ref "DD61") (pin "13") (pinfunction "B3_13") (pintype "passive+no_connect"))
    )
    (net (code "149") (name "unconnected-(DD61-Y3-Pad12)") (class "Default")
      (node (ref "DD61") (pin "12") (pinfunction "Y3_12") (pintype "passive+no_connect"))
    )
    (net (code "150") (name "unconnected-(DD65-Pad1)") (class "Default")
      (node (ref "DD65") (pin "1") (pintype "passive"))
    )
    (net (code "151") (name "unconnected-(DD65-Pad2)") (class "Default")
      (node (ref "DD65") (pin "2") (pintype "passive"))
    )
    (net (code "152") (name "unconnected-(DD65-Pad3)") (class "Default")
      (node (ref "DD65") (pin "3") (pintype "passive"))
    )
    (net (code "153") (name "unconnected-(DD65-Pad4)") (class "Default")
      (node (ref "DD65") (pin "4") (pintype "passive"))
    )
    (net (code "154") (name "unconnected-(DD65-Pad5)") (class "Default")
      (node (ref "DD65") (pin "5") (pintype "passive"))
    )
    (net (code "155") (name "unconnected-(DD65-Pad6)") (class "Default")
      (node (ref "DD65") (pin "6") (pintype "passive"))
    )
    (net (code "156") (name "unconnected-(DD65-Pad8)") (class "Default")
      (node (ref "DD65") (pin "8") (pintype "passive"))
    )
    (net (code "157") (name "unconnected-(DD65-Pad9)") (class "Default")
      (node (ref "DD65") (pin "9") (pintype "passive"))
    )
    (net (code "158") (name "unconnected-(DD65-Pad10)") (class "Default")
      (node (ref "DD65") (pin "10") (pintype "passive"))
    )
  )
)
